# keyboard-adapter-v1_2.net
KiCad netlist of a schematic drawn in EAGLE
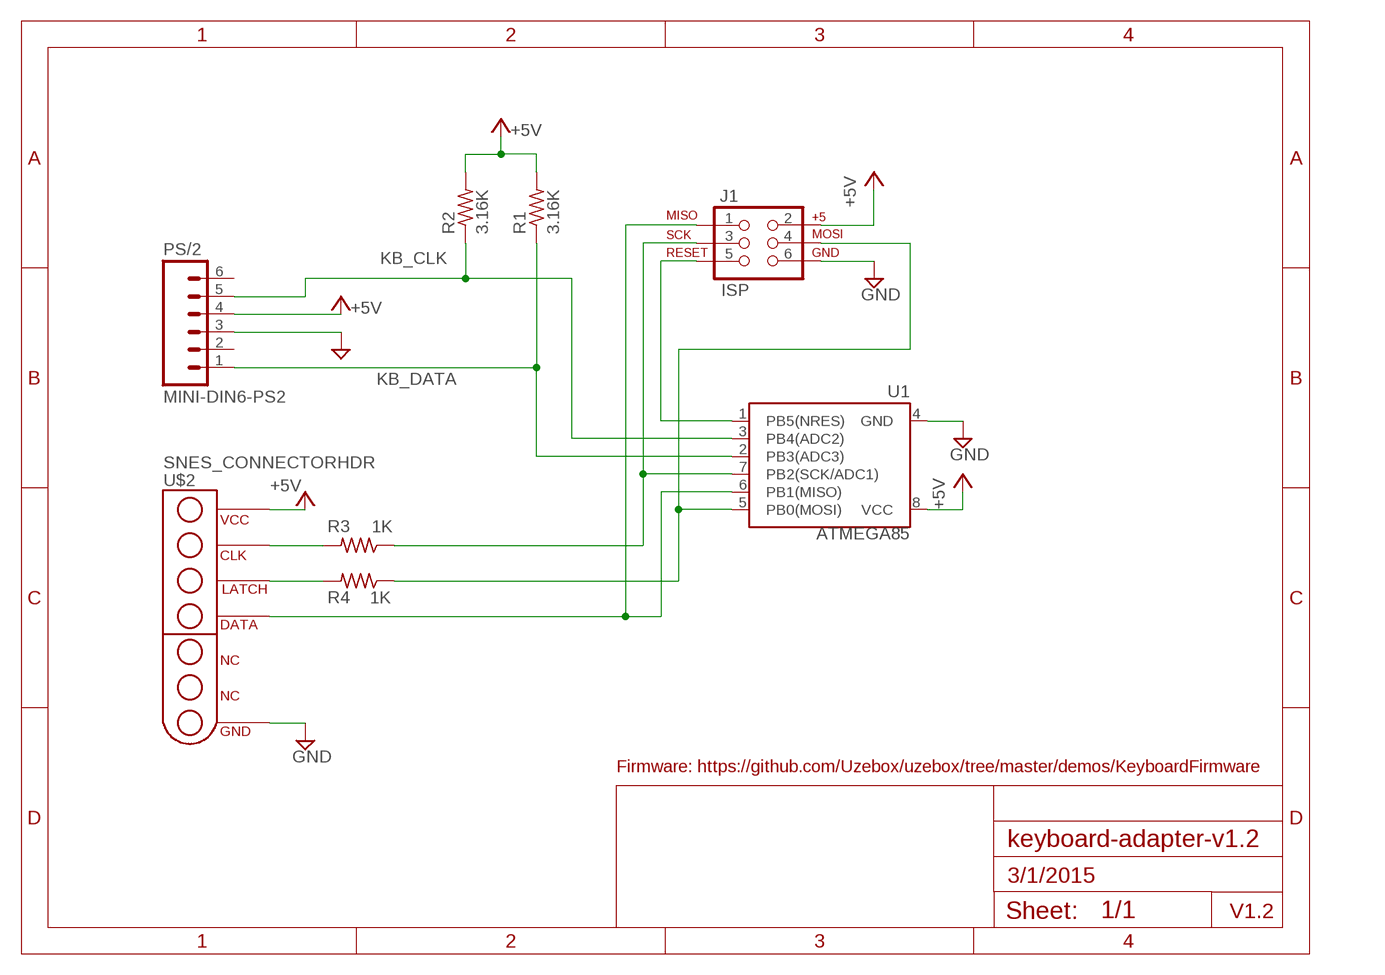
[diagram p0: schematic, sheet 1]

(export (version "E")
  (design (tool "Eeschema 10.0.6"))
  (components
    (comp (ref "ATMEGA85")
      (value "U1")
      (footprint "eagle-import:DIP762W53P254L927H508Q8B")
      (libsource (lib "eagle-import") (part "ATTINY45DIP8"))
    )
    (comp (ref "J1")
      (value "ISP")
      (footprint "eagle-import:2X3")
      (libsource (lib "eagle-import") (part "AVR_SPI_PRG_6-V2PTH"))
    )
    (comp (ref "PS/2")
      (value "MINI-DIN6-PS2")
      (footprint "eagle-import:MINI-DIN6")
      (libsource (lib "eagle-import") (part "MINI-DIN6PTH"))
    )
    (comp (ref "R1")
      (value "3.16K")
      (footprint "eagle-import:0207_10")
      (libsource (lib "eagle-import") (part "R-US_0207/10"))
    )
    (comp (ref "R2")
      (value "3.16K")
      (footprint "eagle-import:0207_10")
      (libsource (lib "eagle-import") (part "R-US_0207/10"))
    )
    (comp (ref "R3")
      (value "1K")
      (footprint "eagle-import:0207_10")
      (libsource (lib "eagle-import") (part "R-US_0207/10"))
    )
    (comp (ref "R4")
      (value "1K")
      (footprint "eagle-import:0207_10")
      (libsource (lib "eagle-import") (part "R-US_0207/10"))
    )
    (comp (ref "U$2")
      (value "SNES_CONNECTORHDR")
      (footprint "eagle-import:SNES_CONN-HDR5")
      (libsource (lib "eagle-import") (part "SNES_CONNECTORHDR"))
    )
  )
  (nets
    (net (code "1") (name "+5V") (class "Default")
      (node (ref "ATMEGA85") (pin "8") (pinfunction "VCC_8") (pintype "bidirectional"))
      (node (ref "J1") (pin "2") (pinfunction "2_2") (pintype "passive"))
      (node (ref "PS/2") (pin "4") (pinfunction "4_4") (pintype "passive"))
      (node (ref "R1") (pin "2") (pinfunction "2_2") (pintype "passive"))
      (node (ref "R2") (pin "2") (pinfunction "2_2") (pintype "passive"))
      (node (ref "U$2") (pin "P$5") (pinfunction "VCC_P$5") (pintype "power_in"))
    )
    (net (code "2") (name "/KB_CLK") (class "Default")
      (node (ref "ATMEGA85") (pin "3") (pinfunction "PB4(ADC2)_3") (pintype "bidirectional"))
      (node (ref "PS/2") (pin "5") (pinfunction "5_5") (pintype "passive"))
      (node (ref "R2") (pin "1") (pinfunction "1_1") (pintype "passive"))
    )
    (net (code "3") (name "/KB_DATA") (class "Default")
      (node (ref "ATMEGA85") (pin "2") (pinfunction "PB3(ADC3)_2") (pintype "bidirectional"))
      (node (ref "PS/2") (pin "1") (pinfunction "1_1") (pintype "passive"))
      (node (ref "R1") (pin "1") (pinfunction "1_1") (pintype "passive"))
    )
    (net (code "4") (name "GND") (class "Default")
      (node (ref "ATMEGA85") (pin "4") (pinfunction "GND_4") (pintype "bidirectional"))
      (node (ref "J1") (pin "6") (pinfunction "6_6") (pintype "passive"))
      (node (ref "PS/2") (pin "3") (pinfunction "3_3") (pintype "passive"))
      (node (ref "U$2") (pin "P$1") (pinfunction "GND_P$1") (pintype "passive"))
    )
    (net (code "5") (name "Net-(ATMEGA85-PB0(MOSI))") (class "Default")
      (node (ref "ATMEGA85") (pin "5") (pinfunction "PB0(MOSI)_5") (pintype "bidirectional"))
      (node (ref "J1") (pin "4") (pinfunction "4_4") (pintype "passive"))
      (node (ref "R4") (pin "1") (pinfunction "1_1") (pintype "passive"))
    )
    (net (code "6") (name "Net-(ATMEGA85-PB1(MISO))") (class "Default")
      (node (ref "ATMEGA85") (pin "6") (pinfunction "PB1(MISO)_6") (pintype "bidirectional"))
      (node (ref "J1") (pin "1") (pinfunction "1_1") (pintype "passive"))
      (node (ref "U$2") (pin "P$2") (pinfunction "DATA_P$2") (pintype "output"))
    )
    (net (code "7") (name "Net-(ATMEGA85-PB2(SCK{slash}ADC1))") (class "Default")
      (node (ref "ATMEGA85") (pin "7") (pinfunction "PB2(SCK/ADC1)_7") (pintype "bidirectional"))
      (node (ref "J1") (pin "3") (pinfunction "3_3") (pintype "passive"))
      (node (ref "R3") (pin "1") (pinfunction "1_1") (pintype "passive"))
    )
    (net (code "8") (name "Net-(ATMEGA85-PB5(NRES))") (class "Default")
      (node (ref "ATMEGA85") (pin "1") (pinfunction "PB5(NRES)_1") (pintype "bidirectional"))
      (node (ref "J1") (pin "5") (pinfunction "5_5") (pintype "passive"))
    )
    (net (code "9") (name "Net-(U$2-CLK)") (class "Default")
      (node (ref "R3") (pin "2") (pinfunction "2_2") (pintype "passive"))
      (node (ref "U$2") (pin "P$4") (pinfunction "CLK_P$4") (pintype "input"))
    )
    (net (code "10") (name "Net-(U$2-LATCH)") (class "Default")
      (node (ref "R4") (pin "2") (pinfunction "2_2") (pintype "passive"))
      (node (ref "U$2") (pin "P$3") (pinfunction "LATCH_P$3") (pintype "input"))
    )
    (net (code "11") (name "unconnected-(PS/2-Pad2)") (class "Default")
      (node (ref "PS/2") (pin "2") (pinfunction "2_2") (pintype "passive"))
    )
    (net (code "12") (name "unconnected-(PS/2-Pad6)") (class "Default")
      (node (ref "PS/2") (pin "6") (pinfunction "6_6") (pintype "passive"))
    )
  )
)
